# PCB-AAP-Robot-Schema.net
KiCad netlist of a schematic drawn in EAGLE
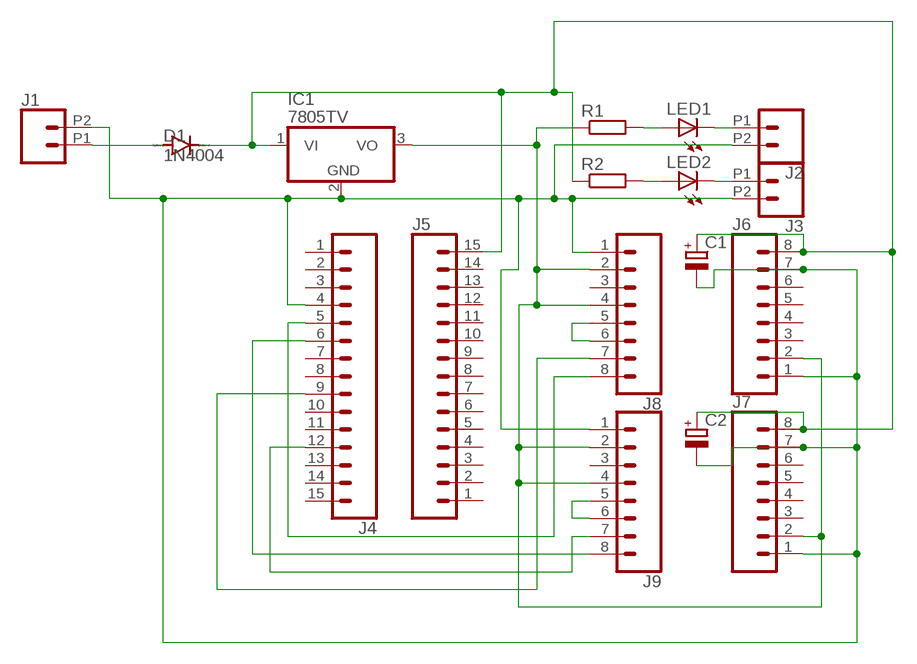
[diagram p0: schematic, sheet 1]

(export (version "E")
  (design (tool "Eeschema 10.0.6"))
  (components
    (comp (ref "C1")
      (value "CPOL-EUB")
      (footprint "eagle-import:PANASONIC_B")
      (libsource (lib "eagle-import") (part "CPOL-EUB"))
    )
    (comp (ref "C2")
      (value "CPOL-EUB")
      (footprint "eagle-import:PANASONIC_B")
      (libsource (lib "eagle-import") (part "CPOL-EUB"))
    )
    (comp (ref "D1")
      (value "1N4004")
      (footprint "eagle-import:DO41-10")
      (libsource (lib "eagle-import") (part "1N4004"))
    )
    (comp (ref "IC1")
      (value "7805TV")
      (footprint "eagle-import:TO220V")
      (libsource (lib "eagle-import") (part "78TV05"))
    )
    (comp (ref "J1")
      (value "CONN_022.54MM_SCREWTERM")
      (footprint "eagle-import:1X02_2.54_SCREWTERM")
      (libsource (lib "eagle-import") (part "CONN_022.54MM_SCREWTERM"))
    )
    (comp (ref "J2")
      (value "CONN_022.54MM_SCREWTERM")
      (footprint "eagle-import:1X02_2.54_SCREWTERM")
      (libsource (lib "eagle-import") (part "CONN_022.54MM_SCREWTERM"))
    )
    (comp (ref "J3")
      (value "CONN_022.54MM_SCREWTERM")
      (footprint "eagle-import:1X02_2.54_SCREWTERM")
      (libsource (lib "eagle-import") (part "CONN_022.54MM_SCREWTERM"))
    )
    (comp (ref "J4")
      (value "CONN_15")
      (footprint "eagle-import:1X15")
      (libsource (lib "eagle-import") (part "CONN_15"))
    )
    (comp (ref "J5")
      (value "CONN_15")
      (footprint "eagle-import:1X15")
      (libsource (lib "eagle-import") (part "CONN_15"))
    )
    (comp (ref "J6")
      (value "CONN_08\"")
      (footprint "eagle-import:1X08")
      (libsource (lib "eagle-import") (part "CONN_08{dblquote}"))
    )
    (comp (ref "J7")
      (value "CONN_08\"")
      (footprint "eagle-import:1X08")
      (libsource (lib "eagle-import") (part "CONN_08{dblquote}"))
    )
    (comp (ref "J8")
      (value "CONN_08\"")
      (footprint "eagle-import:1X08")
      (libsource (lib "eagle-import") (part "CONN_08{dblquote}"))
    )
    (comp (ref "J9")
      (value "CONN_08\"")
      (footprint "eagle-import:1X08")
      (libsource (lib "eagle-import") (part "CONN_08{dblquote}"))
    )
    (comp (ref "LED1")
      (value "LED3MM")
      (footprint "eagle-import:LED3MM")
      (libsource (lib "eagle-import") (part "LED3MM"))
    )
    (comp (ref "LED2")
      (value "LED3MM")
      (footprint "eagle-import:LED3MM")
      (libsource (lib "eagle-import") (part "LED3MM"))
    )
    (comp (ref "R1")
      (value "R-EU_0207/10")
      (footprint "eagle-import:0207_10")
      (libsource (lib "eagle-import") (part "R-EU_0207/10"))
    )
    (comp (ref "R2")
      (value "R-EU_0207/10")
      (footprint "eagle-import:0207_10")
      (libsource (lib "eagle-import") (part "R-EU_0207/10"))
    )
  )
  (nets
    (net (code "1") (name "Net-(IC1-GND)") (class "Default")
      (node (ref "C1") (pin "-") (pinfunction "-_-") (pintype "passive"))
      (node (ref "C2") (pin "-") (pinfunction "-_-") (pintype "passive"))
      (node (ref "IC1") (pin "2") (pinfunction "GND_2") (pintype "passive"))
      (node (ref "J1") (pin "P2") (pinfunction "2_P2") (pintype "passive"))
      (node (ref "J2") (pin "P2") (pinfunction "2_P2") (pintype "passive"))
      (node (ref "J3") (pin "P2") (pinfunction "2_P2") (pintype "passive"))
      (node (ref "J4") (pin "4") (pinfunction "4_4") (pintype "passive"))
      (node (ref "J6") (pin "1") (pinfunction "1_1") (pintype "passive"))
      (node (ref "J6") (pin "7") (pinfunction "7_7") (pintype "passive"))
      (node (ref "J7") (pin "1") (pinfunction "1_1") (pintype "passive"))
      (node (ref "J7") (pin "7") (pinfunction "7_7") (pintype "passive"))
      (node (ref "J8") (pin "1") (pinfunction "1_1") (pintype "passive"))
      (node (ref "J9") (pin "1") (pinfunction "1_1") (pintype "passive"))
    )
    (net (code "2") (name "Net-(IC1-VI)") (class "Default")
      (node (ref "C1") (pin "+") (pinfunction "+_+") (pintype "passive"))
      (node (ref "C2") (pin "+") (pinfunction "+_+") (pintype "passive"))
      (node (ref "D1") (pin "C") (pinfunction "C_C") (pintype "passive"))
      (node (ref "IC1") (pin "1") (pinfunction "VI_1") (pintype "input"))
      (node (ref "J5") (pin "15") (pinfunction "15_15") (pintype "passive"))
      (node (ref "J6") (pin "8") (pinfunction "8_8") (pintype "passive"))
      (node (ref "J7") (pin "8") (pinfunction "8_8") (pintype "passive"))
      (node (ref "R2") (pin "1") (pinfunction "1_1") (pintype "passive"))
    )
    (net (code "3") (name "Net-(IC1-VO)") (class "Default")
      (node (ref "IC1") (pin "3") (pinfunction "VO_3") (pintype "passive"))
      (node (ref "J6") (pin "2") (pinfunction "2_2") (pintype "passive"))
      (node (ref "J7") (pin "2") (pinfunction "2_2") (pintype "passive"))
      (node (ref "J8") (pin "2") (pinfunction "2_2") (pintype "passive"))
      (node (ref "J8") (pin "4") (pinfunction "4_4") (pintype "passive"))
      (node (ref "J9") (pin "2") (pinfunction "2_2") (pintype "passive"))
      (node (ref "J9") (pin "4") (pinfunction "4_4") (pintype "passive"))
      (node (ref "R1") (pin "1") (pinfunction "1_1") (pintype "passive"))
    )
    (net (code "4") (name "Net-(J1-1)") (class "Default")
      (node (ref "D1") (pin "A") (pinfunction "A_A") (pintype "passive"))
      (node (ref "J1") (pin "P1") (pinfunction "1_P1") (pintype "passive"))
    )
    (net (code "5") (name "Net-(J2-1)") (class "Default")
      (node (ref "J2") (pin "P1") (pinfunction "1_P1") (pintype "passive"))
      (node (ref "LED1") (pin "K") (pinfunction "C_K") (pintype "passive"))
    )
    (net (code "6") (name "Net-(J3-1)") (class "Default")
      (node (ref "J3") (pin "P1") (pinfunction "1_P1") (pintype "passive"))
      (node (ref "LED2") (pin "K") (pinfunction "C_K") (pintype "passive"))
    )
    (net (code "7") (name "Net-(J4-Pad5)") (class "Default")
      (node (ref "J4") (pin "5") (pinfunction "5_5") (pintype "passive"))
      (node (ref "J8") (pin "8") (pinfunction "8_8") (pintype "passive"))
    )
    (net (code "8") (name "Net-(J4-Pad6)") (class "Default")
      (node (ref "J4") (pin "6") (pinfunction "6_6") (pintype "passive"))
      (node (ref "J9") (pin "8") (pinfunction "8_8") (pintype "passive"))
    )
    (net (code "9") (name "Net-(J4-Pad9)") (class "Default")
      (node (ref "J4") (pin "9") (pinfunction "9_9") (pintype "passive"))
      (node (ref "J8") (pin "7") (pinfunction "7_7") (pintype "passive"))
    )
    (net (code "10") (name "Net-(J4-Pad12)") (class "Default")
      (node (ref "J4") (pin "12") (pinfunction "12_12") (pintype "passive"))
      (node (ref "J9") (pin "7") (pinfunction "7_7") (pintype "passive"))
    )
    (net (code "11") (name "Net-(J8-Pad5)") (class "Default")
      (node (ref "J8") (pin "5") (pinfunction "5_5") (pintype "passive"))
      (node (ref "J8") (pin "6") (pinfunction "6_6") (pintype "passive"))
    )
    (net (code "12") (name "Net-(J9-Pad5)") (class "Default")
      (node (ref "J9") (pin "5") (pinfunction "5_5") (pintype "passive"))
      (node (ref "J9") (pin "6") (pinfunction "6_6") (pintype "passive"))
    )
    (net (code "13") (name "Net-(LED1-PadA)") (class "Default")
      (node (ref "LED1") (pin "A") (pinfunction "A_A") (pintype "passive"))
      (node (ref "R1") (pin "2") (pinfunction "2_2") (pintype "passive"))
    )
    (net (code "14") (name "Net-(LED2-PadA)") (class "Default")
      (node (ref "LED2") (pin "A") (pinfunction "A_A") (pintype "passive"))
      (node (ref "R2") (pin "2") (pinfunction "2_2") (pintype "passive"))
    )
    (net (code "15") (name "unconnected-(J4-Pad1)") (class "Default")
      (node (ref "J4") (pin "1") (pinfunction "1_1") (pintype "passive"))
    )
    (net (code "16") (name "unconnected-(J4-Pad2)") (class "Default")
      (node (ref "J4") (pin "2") (pinfunction "2_2") (pintype "passive"))
    )
    (net (code "17") (name "unconnected-(J4-Pad3)") (class "Default")
      (node (ref "J4") (pin "3") (pinfunction "3_3") (pintype "passive"))
    )
    (net (code "18") (name "unconnected-(J4-Pad7)") (class "Default")
      (node (ref "J4") (pin "7") (pinfunction "7_7") (pintype "passive"))
    )
    (net (code "19") (name "unconnected-(J4-Pad8)") (class "Default")
      (node (ref "J4") (pin "8") (pinfunction "8_8") (pintype "passive"))
    )
    (net (code "20") (name "unconnected-(J4-Pad10)") (class "Default")
      (node (ref "J4") (pin "10") (pinfunction "10_10") (pintype "passive"))
    )
    (net (code "21") (name "unconnected-(J4-Pad11)") (class "Default")
      (node (ref "J4") (pin "11") (pinfunction "11_11") (pintype "passive"))
    )
    (net (code "22") (name "unconnected-(J4-Pad13)") (class "Default")
      (node (ref "J4") (pin "13") (pinfunction "13_13") (pintype "passive"))
    )
    (net (code "23") (name "unconnected-(J4-Pad14)") (class "Default")
      (node (ref "J4") (pin "14") (pinfunction "14_14") (pintype "passive"))
    )
    (net (code "24") (name "unconnected-(J4-Pad15)") (class "Default")
      (node (ref "J4") (pin "15") (pinfunction "15_15") (pintype "passive"))
    )
    (net (code "25") (name "unconnected-(J5-Pad1)") (class "Default")
      (node (ref "J5") (pin "1") (pinfunction "1_1") (pintype "passive"))
    )
    (net (code "26") (name "unconnected-(J5-Pad2)") (class "Default")
      (node (ref "J5") (pin "2") (pinfunction "2_2") (pintype "passive"))
    )
    (net (code "27") (name "unconnected-(J5-Pad3)") (class "Default")
      (node (ref "J5") (pin "3") (pinfunction "3_3") (pintype "passive"))
    )
    (net (code "28") (name "unconnected-(J5-Pad4)") (class "Default")
      (node (ref "J5") (pin "4") (pinfunction "4_4") (pintype "passive"))
    )
    (net (code "29") (name "unconnected-(J5-Pad5)") (class "Default")
      (node (ref "J5") (pin "5") (pinfunction "5_5") (pintype "passive"))
    )
    (net (code "30") (name "unconnected-(J5-Pad6)") (class "Default")
      (node (ref "J5") (pin "6") (pinfunction "6_6") (pintype "passive"))
    )
    (net (code "31") (name "unconnected-(J5-Pad7)") (class "Default")
      (node (ref "J5") (pin "7") (pinfunction "7_7") (pintype "passive"))
    )
    (net (code "32") (name "unconnected-(J5-Pad8)") (class "Default")
      (node (ref "J5") (pin "8") (pinfunction "8_8") (pintype "passive"))
    )
    (net (code "33") (name "unconnected-(J5-Pad9)") (class "Default")
      (node (ref "J5") (pin "9") (pinfunction "9_9") (pintype "passive"))
    )
    (net (code "34") (name "unconnected-(J5-Pad10)") (class "Default")
      (node (ref "J5") (pin "10") (pinfunction "10_10") (pintype "passive"))
    )
    (net (code "35") (name "unconnected-(J5-Pad11)") (class "Default")
      (node (ref "J5") (pin "11") (pinfunction "11_11") (pintype "passive"))
    )
    (net (code "36") (name "unconnected-(J5-Pad12)") (class "Default")
      (node (ref "J5") (pin "12") (pinfunction "12_12") (pintype "passive"))
    )
    (net (code "37") (name "unconnected-(J5-Pad13)") (class "Default")
      (node (ref "J5") (pin "13") (pinfunction "13_13") (pintype "passive"))
    )
    (net (code "38") (name "unconnected-(J5-Pad14)") (class "Default")
      (node (ref "J5") (pin "14") (pinfunction "14_14") (pintype "passive"))
    )
    (net (code "39") (name "unconnected-(J6-Pad3)") (class "Default")
      (node (ref "J6") (pin "3") (pinfunction "3_3") (pintype "passive"))
    )
    (net (code "40") (name "unconnected-(J6-Pad4)") (class "Default")
      (node (ref "J6") (pin "4") (pinfunction "4_4") (pintype "passive"))
    )
    (net (code "41") (name "unconnected-(J6-Pad5)") (class "Default")
      (node (ref "J6") (pin "5") (pinfunction "5_5") (pintype "passive"))
    )
    (net (code "42") (name "unconnected-(J6-Pad6)") (class "Default")
      (node (ref "J6") (pin "6") (pinfunction "6_6") (pintype "passive"))
    )
    (net (code "43") (name "unconnected-(J7-Pad3)") (class "Default")
      (node (ref "J7") (pin "3") (pinfunction "3_3") (pintype "passive"))
    )
    (net (code "44") (name "unconnected-(J7-Pad4)") (class "Default")
      (node (ref "J7") (pin "4") (pinfunction "4_4") (pintype "passive"))
    )
    (net (code "45") (name "unconnected-(J7-Pad5)") (class "Default")
      (node (ref "J7") (pin "5") (pinfunction "5_5") (pintype "passive"))
    )
    (net (code "46") (name "unconnected-(J7-Pad6)") (class "Default")
      (node (ref "J7") (pin "6") (pinfunction "6_6") (pintype "passive"))
    )
    (net (code "47") (name "unconnected-(J8-Pad3)") (class "Default")
      (node (ref "J8") (pin "3") (pinfunction "3_3") (pintype "passive"))
    )
    (net (code "48") (name "unconnected-(J9-Pad3)") (class "Default")
      (node (ref "J9") (pin "3") (pinfunction "3_3") (pintype "passive"))
    )
  )
)
